# signal_conditioning.net
KiCad netlist of a schematic drawn in Altium Designer
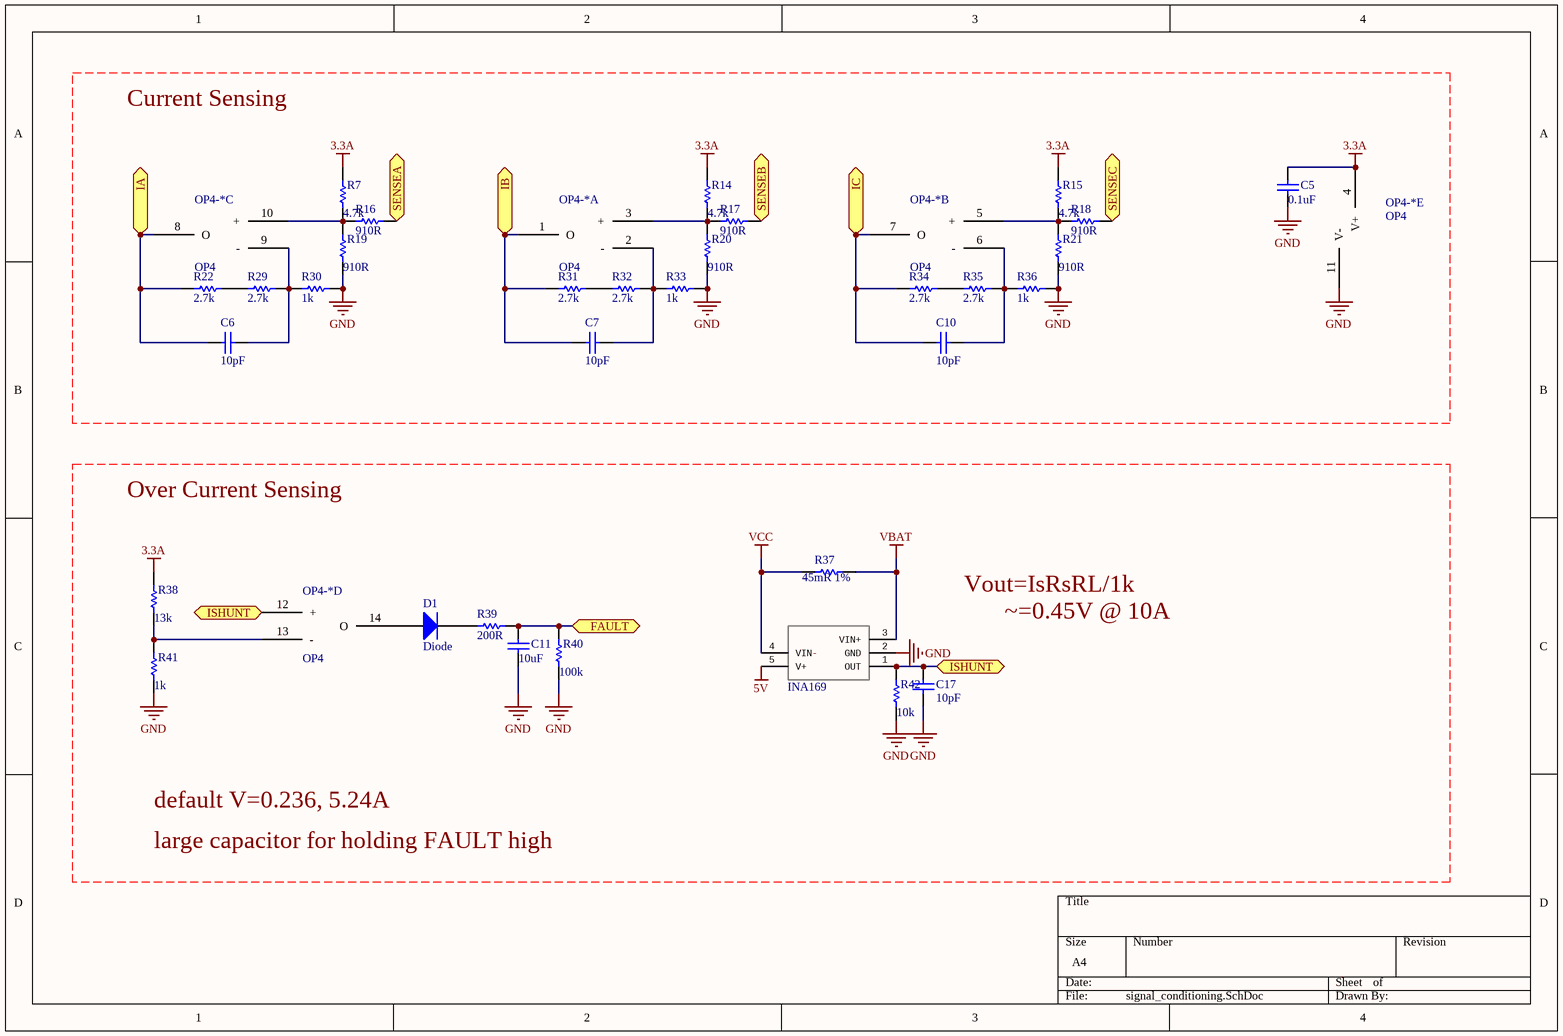
[diagram p0: signal_conditioning.SchDoc]

(export (version "E")
  (design (tool "Eeschema 10.0.6"))
  (components
    (comp (ref "C5")
      (value "0.1uF")
      (footprint "0603")
      (description "Capacitor")
      (fields (field (name "PUBLISHER") "Altium Limited"))
      (libsource (lib "PCB_Project") (part "Cap"))
    )
    (comp (ref "C6")
      (value "10pF")
      (footprint "0603")
      (description "Capacitor")
      (fields (field (name "PUBLISHER") "Altium Limited"))
      (libsource (lib "PCB_Project") (part "Cap"))
    )
    (comp (ref "C7")
      (value "10pF")
      (footprint "0603")
      (description "Capacitor")
      (fields (field (name "PUBLISHER") "Altium Limited"))
      (libsource (lib "PCB_Project") (part "Cap"))
    )
    (comp (ref "C10")
      (value "10pF")
      (footprint "0603")
      (description "Capacitor")
      (fields (field (name "PUBLISHER") "Altium Limited"))
      (libsource (lib "PCB_Project") (part "Cap"))
    )
    (comp (ref "C11")
      (value "10uF")
      (footprint "0805")
      (description "Capacitor")
      (fields (field (name "PUBLISHER") "Altium Limited"))
      (libsource (lib "PCB_Project") (part "Cap"))
    )
    (comp (ref "C17")
      (value "10pF")
      (footprint "0603")
      (description "Capacitor")
      (fields (field (name "PUBLISHER") "Altium Limited"))
      (libsource (lib "PCB_Project") (part "Cap"))
    )
    (comp (ref "D1")
      (value "Diode")
      (footprint "0805")
      (description "Default Diode")
      (fields (field (name "PUBLISHER") "Altium Limited"))
      (libsource (lib "Miscellaneous Devices") (part "Diode"))
    )
    (comp (ref "OP4-*") (value "OP4") (footprint "SOP14") (libsource (lib "sch") (part "OP4")))
    (comp (ref "R7")
      (value "4.7k")
      (footprint "0603")
      (description "Resistor")
      (fields (field (name "PUBLISHER") "Altium Limited"))
      (libsource (lib "Miscellaneous Devices") (part "Res1"))
    )
    (comp (ref "R14")
      (value "4.7k")
      (footprint "0603")
      (description "Resistor")
      (fields (field (name "PUBLISHER") "Altium Limited"))
      (libsource (lib "Miscellaneous Devices") (part "Res1"))
    )
    (comp (ref "R15")
      (value "4.7k")
      (footprint "0603")
      (description "Resistor")
      (fields (field (name "PUBLISHER") "Altium Limited"))
      (libsource (lib "Miscellaneous Devices") (part "Res1"))
    )
    (comp (ref "R16")
      (value "910R")
      (footprint "0603")
      (description "Resistor")
      (fields (field (name "PUBLISHER") "Altium Limited"))
      (libsource (lib "Miscellaneous Devices") (part "Res1"))
    )
    (comp (ref "R17")
      (value "910R")
      (footprint "0603")
      (description "Resistor")
      (fields (field (name "PUBLISHER") "Altium Limited"))
      (libsource (lib "Miscellaneous Devices") (part "Res1"))
    )
    (comp (ref "R18")
      (value "910R")
      (footprint "0603")
      (description "Resistor")
      (fields (field (name "PUBLISHER") "Altium Limited"))
      (libsource (lib "Miscellaneous Devices") (part "Res1"))
    )
    (comp (ref "R19")
      (value "910R")
      (footprint "0603")
      (description "Resistor")
      (fields (field (name "PUBLISHER") "Altium Limited"))
      (libsource (lib "Miscellaneous Devices") (part "Res1"))
    )
    (comp (ref "R20")
      (value "910R")
      (footprint "0603")
      (description "Resistor")
      (fields (field (name "PUBLISHER") "Altium Limited"))
      (libsource (lib "Miscellaneous Devices") (part "Res1"))
    )
    (comp (ref "R21")
      (value "910R")
      (footprint "0603")
      (description "Resistor")
      (fields (field (name "PUBLISHER") "Altium Limited"))
      (libsource (lib "Miscellaneous Devices") (part "Res1"))
    )
    (comp (ref "R22")
      (value "2.7k")
      (footprint "0603")
      (description "Resistor")
      (fields (field (name "PUBLISHER") "Altium Limited"))
      (libsource (lib "Miscellaneous Devices") (part "Res1"))
    )
    (comp (ref "R29")
      (value "2.7k")
      (footprint "0603")
      (description "Resistor")
      (fields (field (name "PUBLISHER") "Altium Limited"))
      (libsource (lib "Miscellaneous Devices") (part "Res1"))
    )
    (comp (ref "R30")
      (value "1k")
      (footprint "0603")
      (description "Resistor")
      (fields (field (name "PUBLISHER") "Altium Limited"))
      (libsource (lib "Miscellaneous Devices") (part "Res1"))
    )
    (comp (ref "R31")
      (value "2.7k")
      (footprint "0603")
      (description "Resistor")
      (fields (field (name "PUBLISHER") "Altium Limited"))
      (libsource (lib "Miscellaneous Devices") (part "Res1"))
    )
    (comp (ref "R32")
      (value "2.7k")
      (footprint "0603")
      (description "Resistor")
      (fields (field (name "PUBLISHER") "Altium Limited"))
      (libsource (lib "Miscellaneous Devices") (part "Res1"))
    )
    (comp (ref "R33")
      (value "1k")
      (footprint "0603")
      (description "Resistor")
      (fields (field (name "PUBLISHER") "Altium Limited"))
      (libsource (lib "Miscellaneous Devices") (part "Res1"))
    )
    (comp (ref "R34")
      (value "2.7k")
      (footprint "0603")
      (description "Resistor")
      (fields (field (name "PUBLISHER") "Altium Limited"))
      (libsource (lib "Miscellaneous Devices") (part "Res1"))
    )
    (comp (ref "R35")
      (value "2.7k")
      (footprint "0603")
      (description "Resistor")
      (fields (field (name "PUBLISHER") "Altium Limited"))
      (libsource (lib "Miscellaneous Devices") (part "Res1"))
    )
    (comp (ref "R36")
      (value "1k")
      (footprint "0603")
      (description "Resistor")
      (fields (field (name "PUBLISHER") "Altium Limited"))
      (libsource (lib "Miscellaneous Devices") (part "Res1"))
    )
    (comp (ref "R37")
      (value "45mR 1%")
      (footprint "2512")
      (description "Resistor")
      (fields (field (name "PUBLISHER") "Altium Limited"))
      (libsource (lib "Miscellaneous Devices") (part "Res1"))
    )
    (comp (ref "R38")
      (value "13k")
      (footprint "0603")
      (description "Resistor")
      (fields (field (name "PUBLISHER") "Altium Limited"))
      (libsource (lib "Miscellaneous Devices") (part "Res1"))
    )
    (comp (ref "R39")
      (value "200R")
      (footprint "0603")
      (description "Resistor")
      (fields (field (name "PUBLISHER") "Altium Limited"))
      (libsource (lib "Miscellaneous Devices") (part "Res1"))
    )
    (comp (ref "R40")
      (value "100k")
      (footprint "0603")
      (description "Resistor")
      (fields (field (name "PUBLISHER") "Altium Limited"))
      (libsource (lib "Miscellaneous Devices") (part "Res1"))
    )
    (comp (ref "R41")
      (value "1k")
      (footprint "0603")
      (description "Resistor")
      (fields (field (name "PUBLISHER") "Altium Limited"))
      (libsource (lib "Miscellaneous Devices") (part "Res1"))
    )
    (comp (ref "R42")
      (value "10k")
      (footprint "0603")
      (description "Resistor")
      (fields (field (name "PUBLISHER") "Altium Limited"))
      (libsource (lib "Miscellaneous Devices") (part "Res1"))
    )
    (comp (ref "U$1") (value "INA169") (footprint "SOT23-5") (libsource (lib "sch") (part "INA169")))
  )
  (nets
    (net (code "1") (name "/FAULT") (class "Default")
      (node (ref "C11") (pin "1") (pinfunction "1_1") (pintype "passive"))
      (node (ref "R39") (pin "1") (pinfunction "1_1") (pintype "passive"))
      (node (ref "R40") (pin "2") (pinfunction "2_2") (pintype "passive"))
    )
    (net (code "2") (name "/IA") (class "Default")
      (node (ref "C6") (pin "1") (pinfunction "1_1") (pintype "passive"))
      (node (ref "OP4-*") (pin "8") (pinfunction "O_8") (pintype "passive"))
      (node (ref "R22") (pin "2") (pinfunction "2_2") (pintype "passive"))
    )
    (net (code "3") (name "/IB") (class "Default")
      (node (ref "C7") (pin "1") (pinfunction "1_1") (pintype "passive"))
      (node (ref "OP4-*") (pin "1") (pinfunction "O_1") (pintype "passive"))
      (node (ref "R31") (pin "2") (pinfunction "2_2") (pintype "passive"))
    )
    (net (code "4") (name "/IC") (class "Default")
      (node (ref "C10") (pin "1") (pinfunction "1_1") (pintype "passive"))
      (node (ref "OP4-*") (pin "7") (pinfunction "O_7") (pintype "passive"))
      (node (ref "R34") (pin "2") (pinfunction "2_2") (pintype "passive"))
    )
    (net (code "5") (name "/ISHUNT") (class "Default")
      (node (ref "C17") (pin "2") (pinfunction "2_2") (pintype "passive"))
      (node (ref "OP4-*") (pin "12") (pinfunction "+_12") (pintype "passive"))
      (node (ref "R42") (pin "2") (pinfunction "2_2") (pintype "passive"))
      (node (ref "U$1") (pin "1") (pinfunction "OUT_1") (pintype "passive"))
    )
    (net (code "6") (name "/SENSEA") (class "Default")
      (node (ref "R16") (pin "1") (pinfunction "1_1") (pintype "passive"))
    )
    (net (code "7") (name "/SENSEB") (class "Default")
      (node (ref "R17") (pin "1") (pinfunction "1_1") (pintype "passive"))
    )
    (net (code "8") (name "/SENSEC") (class "Default")
      (node (ref "R18") (pin "1") (pinfunction "1_1") (pintype "passive"))
    )
    (net (code "9") (name "3.3A") (class "Default")
      (node (ref "C5") (pin "1") (pinfunction "1_1") (pintype "passive"))
      (node (ref "OP4-*") (pin "4") (pinfunction "V+_4") (pintype "passive"))
      (node (ref "R14") (pin "2") (pinfunction "2_2") (pintype "passive"))
      (node (ref "R15") (pin "2") (pinfunction "2_2") (pintype "passive"))
      (node (ref "R38") (pin "2") (pinfunction "2_2") (pintype "passive"))
      (node (ref "R7") (pin "2") (pinfunction "2_2") (pintype "passive"))
    )
    (net (code "10") (name "5V") (class "Default")
      (node (ref "U$1") (pin "5") (pinfunction "V+_5") (pintype "passive"))
    )
    (net (code "11") (name "GND") (class "Default")
      (node (ref "C11") (pin "2") (pinfunction "2_2") (pintype "passive"))
      (node (ref "C17") (pin "1") (pinfunction "1_1") (pintype "passive"))
      (node (ref "C5") (pin "2") (pinfunction "2_2") (pintype "passive"))
      (node (ref "OP4-*") (pin "11") (pinfunction "V-_11") (pintype "passive"))
      (node (ref "R19") (pin "1") (pinfunction "1_1") (pintype "passive"))
      (node (ref "R20") (pin "1") (pinfunction "1_1") (pintype "passive"))
      (node (ref "R21") (pin "1") (pinfunction "1_1") (pintype "passive"))
      (node (ref "R30") (pin "1") (pinfunction "1_1") (pintype "passive"))
      (node (ref "R33") (pin "1") (pinfunction "1_1") (pintype "passive"))
      (node (ref "R36") (pin "1") (pinfunction "1_1") (pintype "passive"))
      (node (ref "R40") (pin "1") (pinfunction "1_1") (pintype "passive"))
      (node (ref "R41") (pin "1") (pinfunction "1_1") (pintype "passive"))
      (node (ref "R42") (pin "1") (pinfunction "1_1") (pintype "passive"))
      (node (ref "U$1") (pin "2") (pinfunction "GND_2") (pintype "passive"))
    )
    (net (code "12") (name "Net-(D1-A)") (class "Default")
      (node (ref "D1") (pin "1") (pinfunction "A_1") (pintype "passive"))
      (node (ref "OP4-*") (pin "14") (pinfunction "O_14") (pintype "passive"))
    )
    (net (code "13") (name "Net-(D1-K)") (class "Default")
      (node (ref "D1") (pin "2") (pinfunction "K_2") (pintype "passive"))
      (node (ref "R39") (pin "2") (pinfunction "2_2") (pintype "passive"))
    )
    (net (code "14") (name "Net-(OP4-*A-+)") (class "Default")
      (node (ref "OP4-*") (pin "3") (pinfunction "+_3") (pintype "passive"))
      (node (ref "R14") (pin "1") (pinfunction "1_1") (pintype "passive"))
      (node (ref "R17") (pin "2") (pinfunction "2_2") (pintype "passive"))
      (node (ref "R20") (pin "2") (pinfunction "2_2") (pintype "passive"))
    )
    (net (code "15") (name "Net-(OP4-*A--)") (class "Default")
      (node (ref "C7") (pin "2") (pinfunction "2_2") (pintype "passive"))
      (node (ref "OP4-*") (pin "2") (pinfunction "-_2") (pintype "passive"))
      (node (ref "R32") (pin "1") (pinfunction "1_1") (pintype "passive"))
      (node (ref "R33") (pin "2") (pinfunction "2_2") (pintype "passive"))
    )
    (net (code "16") (name "Net-(OP4-*B-+)") (class "Default")
      (node (ref "OP4-*") (pin "5") (pinfunction "+_5") (pintype "passive"))
      (node (ref "R15") (pin "1") (pinfunction "1_1") (pintype "passive"))
      (node (ref "R18") (pin "2") (pinfunction "2_2") (pintype "passive"))
      (node (ref "R21") (pin "2") (pinfunction "2_2") (pintype "passive"))
    )
    (net (code "17") (name "Net-(OP4-*B--)") (class "Default")
      (node (ref "C10") (pin "2") (pinfunction "2_2") (pintype "passive"))
      (node (ref "OP4-*") (pin "6") (pinfunction "-_6") (pintype "passive"))
      (node (ref "R35") (pin "1") (pinfunction "1_1") (pintype "passive"))
      (node (ref "R36") (pin "2") (pinfunction "2_2") (pintype "passive"))
    )
    (net (code "18") (name "Net-(OP4-*C-+)") (class "Default")
      (node (ref "OP4-*") (pin "10") (pinfunction "+_10") (pintype "passive"))
      (node (ref "R16") (pin "2") (pinfunction "2_2") (pintype "passive"))
      (node (ref "R19") (pin "2") (pinfunction "2_2") (pintype "passive"))
      (node (ref "R7") (pin "1") (pinfunction "1_1") (pintype "passive"))
    )
    (net (code "19") (name "Net-(OP4-*C--)") (class "Default")
      (node (ref "C6") (pin "2") (pinfunction "2_2") (pintype "passive"))
      (node (ref "OP4-*") (pin "9") (pinfunction "-_9") (pintype "passive"))
      (node (ref "R29") (pin "1") (pinfunction "1_1") (pintype "passive"))
      (node (ref "R30") (pin "2") (pinfunction "2_2") (pintype "passive"))
    )
    (net (code "20") (name "Net-(OP4-*D--)") (class "Default")
      (node (ref "OP4-*") (pin "13") (pinfunction "-_13") (pintype "passive"))
      (node (ref "R38") (pin "1") (pinfunction "1_1") (pintype "passive"))
      (node (ref "R41") (pin "2") (pinfunction "2_2") (pintype "passive"))
    )
    (net (code "21") (name "Net-(R22-Pad1)") (class "Default")
      (node (ref "R22") (pin "1") (pinfunction "1_1") (pintype "passive"))
      (node (ref "R29") (pin "2") (pinfunction "2_2") (pintype "passive"))
    )
    (net (code "22") (name "Net-(R31-Pad1)") (class "Default")
      (node (ref "R31") (pin "1") (pinfunction "1_1") (pintype "passive"))
      (node (ref "R32") (pin "2") (pinfunction "2_2") (pintype "passive"))
    )
    (net (code "23") (name "Net-(R34-Pad1)") (class "Default")
      (node (ref "R34") (pin "1") (pinfunction "1_1") (pintype "passive"))
      (node (ref "R35") (pin "2") (pinfunction "2_2") (pintype "passive"))
    )
    (net (code "24") (name "VBAT") (class "Default")
      (node (ref "R37") (pin "2") (pinfunction "2_2") (pintype "passive"))
      (node (ref "U$1") (pin "3") (pinfunction "VIN+_3") (pintype "passive"))
    )
    (net (code "25") (name "VCC") (class "Default")
      (node (ref "R37") (pin "1") (pinfunction "1_1") (pintype "passive"))
      (node (ref "U$1") (pin "4") (pinfunction "VIN-_4") (pintype "passive"))
    )
  )
)
